# mini-in-a-1.net
KiCad netlist of a schematic drawn in EAGLE
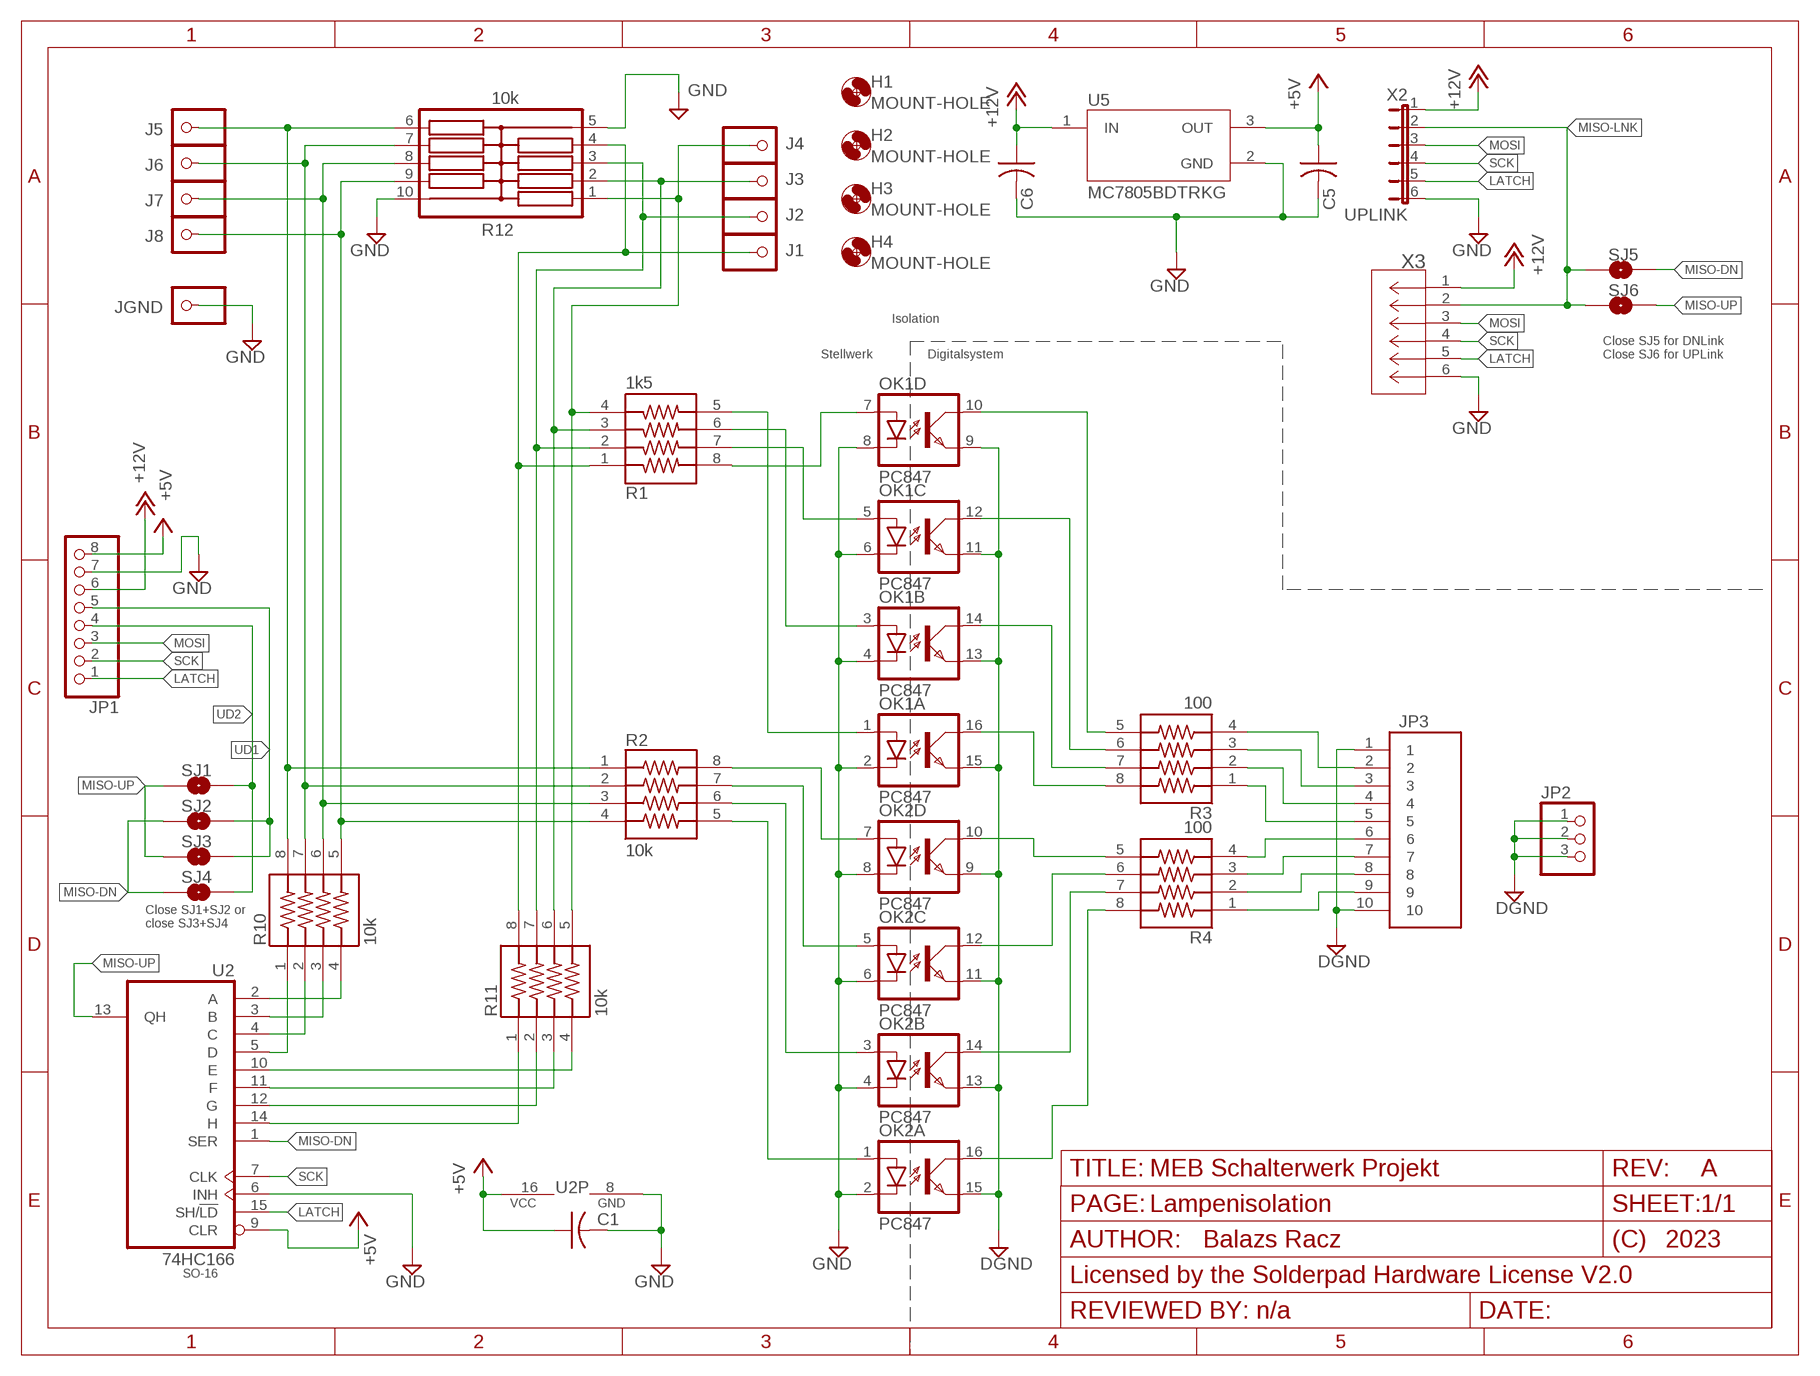
[diagram p0: schematic, sheet 1]

(export (version "E")
  (design (tool "Eeschema 10.0.6"))
  (components
    (comp (ref "C1")
      (value "C-USC0805")
      (footprint "eagle-import:C0805")
      (libsource (lib "eagle-import") (part "C-USC0805"))
    )
    (comp (ref "C5")
      (value "C-USC0805")
      (footprint "eagle-import:C0805")
      (libsource (lib "eagle-import") (part "C-USC0805"))
    )
    (comp (ref "C6")
      (value "C-USC0805")
      (footprint "eagle-import:C0805")
      (libsource (lib "eagle-import") (part "C-USC0805"))
    )
    (comp (ref "H1")
      (value "MOUNT-HOLE")
      (footprint "eagle-import:MOUNT-HOLE-2,8")
      (libsource (lib "eagle-import") (part "MOUNT-HOLE"))
    )
    (comp (ref "H2")
      (value "MOUNT-HOLE")
      (footprint "eagle-import:MOUNT-HOLE-2,8")
      (libsource (lib "eagle-import") (part "MOUNT-HOLE"))
    )
    (comp (ref "H3")
      (value "MOUNT-HOLE")
      (footprint "eagle-import:MOUNT-HOLE-2,8")
      (libsource (lib "eagle-import") (part "MOUNT-HOLE"))
    )
    (comp (ref "H4")
      (value "MOUNT-HOLE")
      (footprint "eagle-import:MOUNT-HOLE-2,8")
      (libsource (lib "eagle-import") (part "MOUNT-HOLE"))
    )
    (comp (ref "J1")
      (value "LARGE-SOLDERPADWITH-HOLE")
      (footprint "eagle-import:LARGE-SOLDERPAD-WITH-HOLES")
      (libsource (lib "eagle-import") (part "LARGE-SOLDERPADWITH-HOLE"))
    )
    (comp (ref "J2")
      (value "LARGE-SOLDERPADWITH-HOLE")
      (footprint "eagle-import:LARGE-SOLDERPAD-WITH-HOLES")
      (libsource (lib "eagle-import") (part "LARGE-SOLDERPADWITH-HOLE"))
    )
    (comp (ref "J3")
      (value "LARGE-SOLDERPADWITH-HOLE")
      (footprint "eagle-import:LARGE-SOLDERPAD-WITH-HOLES")
      (libsource (lib "eagle-import") (part "LARGE-SOLDERPADWITH-HOLE"))
    )
    (comp (ref "J4")
      (value "LARGE-SOLDERPADWITH-HOLE")
      (footprint "eagle-import:LARGE-SOLDERPAD-WITH-HOLES")
      (libsource (lib "eagle-import") (part "LARGE-SOLDERPADWITH-HOLE"))
    )
    (comp (ref "J5")
      (value "LARGE-SOLDERPADWITH-HOLE")
      (footprint "eagle-import:LARGE-SOLDERPAD-WITH-HOLES")
      (libsource (lib "eagle-import") (part "LARGE-SOLDERPADWITH-HOLE"))
    )
    (comp (ref "J6")
      (value "LARGE-SOLDERPADWITH-HOLE")
      (footprint "eagle-import:LARGE-SOLDERPAD-WITH-HOLES")
      (libsource (lib "eagle-import") (part "LARGE-SOLDERPADWITH-HOLE"))
    )
    (comp (ref "J7")
      (value "LARGE-SOLDERPADWITH-HOLE")
      (footprint "eagle-import:LARGE-SOLDERPAD-WITH-HOLES")
      (libsource (lib "eagle-import") (part "LARGE-SOLDERPADWITH-HOLE"))
    )
    (comp (ref "J8")
      (value "LARGE-SOLDERPADWITH-HOLE")
      (footprint "eagle-import:LARGE-SOLDERPAD-WITH-HOLES")
      (libsource (lib "eagle-import") (part "LARGE-SOLDERPADWITH-HOLE"))
    )
    (comp (ref "JGND")
      (value "LARGE-SOLDERPADWITH-HOLE")
      (footprint "eagle-import:LARGE-SOLDERPAD-WITH-HOLES")
      (libsource (lib "eagle-import") (part "LARGE-SOLDERPADWITH-HOLE"))
    )
    (comp (ref "JP1")
      (value "PINHD-1X8")
      (footprint "eagle-import:1X08")
      (libsource (lib "eagle-import") (part "PINHD-1X8"))
    )
    (comp (ref "JP2")
      (value "PINHD-1X3")
      (footprint "eagle-import:1X03")
      (libsource (lib "eagle-import") (part "PINHD-1X3"))
    )
    (comp (ref "JP3")
      (value "TE-CON-MTA150-RA-HEADER-1-640457-0")
      (footprint "eagle-import:TE_1-640457-0")
      (fields (field (name "MANUFACTURER") "TE"))
      (libsource (lib "eagle-import") (part "TE-CON-MTA150-RA-HEADER-1-640457-0"))
    )
    (comp (ref "OK1")
      (value "PC847")
      (footprint "eagle-import:DIL16")
      (libsource (lib "eagle-import") (part "PC847"))
    )
    (comp (ref "OK2")
      (value "PC847")
      (footprint "eagle-import:DIL16")
      (libsource (lib "eagle-import") (part "PC847"))
    )
    (comp (ref "R1")
      (value "1k5")
      (footprint "eagle-import:RESCAXS127P508X320X70-8N")
      (fields (field (name "MANUFACTURER") "Yageo"))
      (libsource (lib "eagle-import") (part "RES-NET-YC324-JK-0710KL"))
    )
    (comp (ref "R2")
      (value "10k")
      (footprint "eagle-import:RESCAXS127P508X320X70-8N")
      (fields (field (name "MANUFACTURER") "Yageo"))
      (libsource (lib "eagle-import") (part "RES-NET-YC324-JK-0710KL"))
    )
    (comp (ref "R3")
      (value "100")
      (footprint "eagle-import:RESCAXS127P508X320X70-8N")
      (fields (field (name "MANUFACTURER") "Yageo"))
      (libsource (lib "eagle-import") (part "RES-NET-YC324-JK-0710KL"))
    )
    (comp (ref "R4")
      (value "100")
      (footprint "eagle-import:RESCAXS127P508X320X70-8N")
      (fields (field (name "MANUFACTURER") "Yageo"))
      (libsource (lib "eagle-import") (part "RES-NET-YC324-JK-0710KL"))
    )
    (comp (ref "R10")
      (value "10k")
      (footprint "eagle-import:RESCAXS127P508X320X70-8N")
      (fields (field (name "MANUFACTURER") "Yageo"))
      (libsource (lib "eagle-import") (part "RES-NET-YC324-JK-0710KL"))
    )
    (comp (ref "R11")
      (value "10k")
      (footprint "eagle-import:RESCAXS127P508X320X70-8N")
      (fields (field (name "MANUFACTURER") "Yageo"))
      (libsource (lib "eagle-import") (part "RES-NET-YC324-JK-0710KL"))
    )
    (comp (ref "R12")
      (value "10k")
      (footprint "eagle-import:RESCAV127P640X310X70-10N")
      (fields (field (name "MANUFACTURER") "CTS"))
      (libsource (lib "eagle-import") (part "RES-NET-745C101103JP"))
    )
    (comp (ref "SJ1")
      (value "SJRND2")
      (footprint "eagle-import:SJ_RND2")
      (libsource (lib "eagle-import") (part "SJRND2"))
    )
    (comp (ref "SJ2")
      (value "SJRND2")
      (footprint "eagle-import:SJ_RND2")
      (libsource (lib "eagle-import") (part "SJRND2"))
    )
    (comp (ref "SJ3")
      (value "SJRND2")
      (footprint "eagle-import:SJ_RND2")
      (libsource (lib "eagle-import") (part "SJRND2"))
    )
    (comp (ref "SJ4")
      (value "SJRND2")
      (footprint "eagle-import:SJ_RND2")
      (libsource (lib "eagle-import") (part "SJRND2"))
    )
    (comp (ref "SJ5")
      (value "SJRND2")
      (footprint "eagle-import:SJ_RND2")
      (libsource (lib "eagle-import") (part "SJRND2"))
    )
    (comp (ref "SJ6")
      (value "SJRND2")
      (footprint "eagle-import:SJ_RND2")
      (libsource (lib "eagle-import") (part "SJRND2"))
    )
    (comp (ref "U2")
      (value "74HC166")
      (footprint "eagle-import:SO16")
      (libsource (lib "eagle-import") (part "74166D"))
    )
    (comp (ref "U5")
      (value "MC7805BDTRKG")
      (footprint "eagle-import:DPAK229P990X238-4N")
      (fields (field (name "MANUFACTURER") "ON Semiconductor"))
      (libsource (lib "eagle-import") (part "MC7805BDTRKG"))
    )
    (comp (ref "X2")
      (value "UPLINK")
      (footprint "eagle-import:JP6F-FEM")
      (libsource (lib "eagle-import") (part "JP6-FLATFEMALE"))
    )
    (comp (ref "X3")
      (value "MOLEX_530480610CON_530480610_MOL")
      (footprint "eagle-import:CON_530480610_MOL")
      (fields
        (field (name "MANUFACTURER_PART_NUMBER") "530480610")
        (field (name "COPYRIGHT") "Copyright (C) 2023 Ultra Librarian. All rights reserved.")
      )
      (libsource (lib "eagle-import") (part "MOLEX_530480610CON_530480610_MOL"))
    )
  )
  (nets
    (net (code "1") (name "+5V") (class "Default")
      (node (ref "C1") (pin "1") (pinfunction "1_1") (pintype "passive"))
      (node (ref "C5") (pin "1") (pinfunction "1_1") (pintype "passive"))
      (node (ref "JP1") (pin "8") (pinfunction "8_8") (pintype "passive"))
      (node (ref "U2") (pin "16") (pinfunction "VCC_16") (pintype "power_in"))
      (node (ref "U2") (pin "9") (pinfunction "CLR_9") (pintype "input"))
      (node (ref "U5") (pin "3") (pinfunction "OUT_3") (pintype "output"))
    )
    (net (code "2") (name "+12V") (class "Default")
      (node (ref "C6") (pin "1") (pinfunction "1_1") (pintype "passive"))
      (node (ref "JP1") (pin "6") (pinfunction "6_6") (pintype "passive"))
      (node (ref "U5") (pin "1") (pinfunction "IN_1") (pintype "input"))
      (node (ref "X2") (pin "1") (pinfunction "1_1") (pintype "passive"))
      (node (ref "X3") (pin "1") (pinfunction "1_1") (pintype "passive"))
    )
    (net (code "3") (name "DGND") (class "Default")
      (node (ref "JP2") (pin "1") (pinfunction "1_1") (pintype "passive"))
      (node (ref "JP2") (pin "2") (pinfunction "2_2") (pintype "passive"))
      (node (ref "JP2") (pin "3") (pinfunction "3_3") (pintype "passive"))
      (node (ref "JP3") (pin "1") (pinfunction "1_1") (pintype "passive"))
      (node (ref "JP3") (pin "10") (pinfunction "10_10") (pintype "passive"))
      (node (ref "OK1") (pin "11") (pinfunction "EMIT_11") (pintype "passive"))
      (node (ref "OK1") (pin "13") (pinfunction "EMIT_13") (pintype "passive"))
      (node (ref "OK1") (pin "15") (pinfunction "EMIT_15") (pintype "passive"))
      (node (ref "OK1") (pin "9") (pinfunction "EMIT_9") (pintype "passive"))
      (node (ref "OK2") (pin "11") (pinfunction "EMIT_11") (pintype "passive"))
      (node (ref "OK2") (pin "13") (pinfunction "EMIT_13") (pintype "passive"))
      (node (ref "OK2") (pin "15") (pinfunction "EMIT_15") (pintype "passive"))
      (node (ref "OK2") (pin "9") (pinfunction "EMIT_9") (pintype "passive"))
    )
    (net (code "4") (name "GND") (class "Default")
      (node (ref "C1") (pin "2") (pinfunction "2_2") (pintype "passive"))
      (node (ref "C5") (pin "2") (pinfunction "2_2") (pintype "passive"))
      (node (ref "C6") (pin "2") (pinfunction "2_2") (pintype "passive"))
      (node (ref "JGND") (pin "P$1") (pinfunction "1_P$1") (pintype "passive"))
      (node (ref "JP1") (pin "7") (pinfunction "7_7") (pintype "passive"))
      (node (ref "OK1") (pin "2") (pinfunction "C_2") (pintype "passive"))
      (node (ref "OK1") (pin "4") (pinfunction "C_4") (pintype "passive"))
      (node (ref "OK1") (pin "6") (pinfunction "C_6") (pintype "passive"))
      (node (ref "OK1") (pin "8") (pinfunction "C_8") (pintype "passive"))
      (node (ref "OK2") (pin "2") (pinfunction "C_2") (pintype "passive"))
      (node (ref "OK2") (pin "4") (pinfunction "C_4") (pintype "passive"))
      (node (ref "OK2") (pin "6") (pinfunction "C_6") (pintype "passive"))
      (node (ref "OK2") (pin "8") (pinfunction "C_8") (pintype "passive"))
      (node (ref "R12") (pin "10") (pinfunction "10_10") (pintype "passive"))
      (node (ref "R12") (pin "5") (pinfunction "5_5") (pintype "passive"))
      (node (ref "U2") (pin "6") (pinfunction "INH_6") (pintype "input"))
      (node (ref "U2") (pin "8") (pinfunction "GND_8") (pintype "power_in"))
      (node (ref "U5") (pin "2") (pinfunction "GND_2") (pintype "power_in"))
      (node (ref "X2") (pin "6") (pinfunction "6_6") (pintype "passive"))
      (node (ref "X3") (pin "6") (pinfunction "6_6") (pintype "passive"))
    )
    (net (code "5") (name "LATCH") (class "Default")
      (node (ref "JP1") (pin "1") (pinfunction "1_1") (pintype "passive"))
      (node (ref "U2") (pin "15") (pinfunction "SH/~{LD}_15") (pintype "input"))
      (node (ref "X2") (pin "5") (pinfunction "5_5") (pintype "passive"))
      (node (ref "X3") (pin "5") (pinfunction "5_5") (pintype "passive"))
    )
    (net (code "6") (name "MISO-DN") (class "Default")
      (node (ref "SJ2") (pin "P$1") (pinfunction "1_P$1") (pintype "passive"))
      (node (ref "SJ4") (pin "P$1") (pinfunction "1_P$1") (pintype "passive"))
      (node (ref "SJ5") (pin "P$1") (pinfunction "1_P$1") (pintype "passive"))
      (node (ref "U2") (pin "1") (pinfunction "SER_1") (pintype "input"))
    )
    (net (code "7") (name "MISO-LNK") (class "Default")
      (node (ref "SJ5") (pin "P$2") (pinfunction "2_P$2") (pintype "passive"))
      (node (ref "SJ6") (pin "P$2") (pinfunction "2_P$2") (pintype "passive"))
      (node (ref "X2") (pin "2") (pinfunction "2_2") (pintype "passive"))
      (node (ref "X3") (pin "2") (pinfunction "2_2") (pintype "passive"))
    )
    (net (code "8") (name "MISO-UP") (class "Default")
      (node (ref "SJ1") (pin "P$1") (pinfunction "1_P$1") (pintype "passive"))
      (node (ref "SJ3") (pin "P$1") (pinfunction "1_P$1") (pintype "passive"))
      (node (ref "SJ6") (pin "P$1") (pinfunction "1_P$1") (pintype "passive"))
      (node (ref "U2") (pin "13") (pinfunction "QH_13") (pintype "output"))
    )
    (net (code "9") (name "MOSI") (class "Default")
      (node (ref "JP1") (pin "3") (pinfunction "3_3") (pintype "passive"))
      (node (ref "X2") (pin "3") (pinfunction "3_3") (pintype "passive"))
      (node (ref "X3") (pin "3") (pinfunction "3_3") (pintype "passive"))
    )
    (net (code "10") (name "Net-(J1-1)") (class "Default")
      (node (ref "J1") (pin "P$1") (pinfunction "1_P$1") (pintype "passive"))
      (node (ref "R1") (pin "1") (pinfunction "1_1") (pintype "passive"))
      (node (ref "R11") (pin "8") (pinfunction "8_8") (pintype "passive"))
      (node (ref "R12") (pin "4") (pinfunction "4_4") (pintype "passive"))
    )
    (net (code "11") (name "Net-(J2-1)") (class "Default")
      (node (ref "J2") (pin "P$1") (pinfunction "1_P$1") (pintype "passive"))
      (node (ref "R1") (pin "2") (pinfunction "2_2") (pintype "passive"))
      (node (ref "R11") (pin "7") (pinfunction "7_7") (pintype "passive"))
      (node (ref "R12") (pin "3") (pinfunction "3_3") (pintype "passive"))
    )
    (net (code "12") (name "Net-(J3-1)") (class "Default")
      (node (ref "J3") (pin "P$1") (pinfunction "1_P$1") (pintype "passive"))
      (node (ref "R1") (pin "3") (pinfunction "3_3") (pintype "passive"))
      (node (ref "R11") (pin "6") (pinfunction "6_6") (pintype "passive"))
      (node (ref "R12") (pin "2") (pinfunction "2_2") (pintype "passive"))
    )
    (net (code "13") (name "Net-(J4-1)") (class "Default")
      (node (ref "J4") (pin "P$1") (pinfunction "1_P$1") (pintype "passive"))
      (node (ref "R1") (pin "4") (pinfunction "4_4") (pintype "passive"))
      (node (ref "R11") (pin "5") (pinfunction "5_5") (pintype "passive"))
      (node (ref "R12") (pin "1") (pinfunction "1_1") (pintype "passive"))
    )
    (net (code "14") (name "Net-(J5-1)") (class "Default")
      (node (ref "J5") (pin "P$1") (pinfunction "1_P$1") (pintype "passive"))
      (node (ref "R10") (pin "8") (pinfunction "8_8") (pintype "passive"))
      (node (ref "R12") (pin "6") (pinfunction "6_6") (pintype "passive"))
      (node (ref "R2") (pin "1") (pinfunction "1_1") (pintype "passive"))
    )
    (net (code "15") (name "Net-(J6-1)") (class "Default")
      (node (ref "J6") (pin "P$1") (pinfunction "1_P$1") (pintype "passive"))
      (node (ref "R10") (pin "7") (pinfunction "7_7") (pintype "passive"))
      (node (ref "R12") (pin "7") (pinfunction "7_7") (pintype "passive"))
      (node (ref "R2") (pin "2") (pinfunction "2_2") (pintype "passive"))
    )
    (net (code "16") (name "Net-(J7-1)") (class "Default")
      (node (ref "J7") (pin "P$1") (pinfunction "1_P$1") (pintype "passive"))
      (node (ref "R10") (pin "6") (pinfunction "6_6") (pintype "passive"))
      (node (ref "R12") (pin "8") (pinfunction "8_8") (pintype "passive"))
      (node (ref "R2") (pin "3") (pinfunction "3_3") (pintype "passive"))
    )
    (net (code "17") (name "Net-(J8-1)") (class "Default")
      (node (ref "J8") (pin "P$1") (pinfunction "1_P$1") (pintype "passive"))
      (node (ref "R10") (pin "5") (pinfunction "5_5") (pintype "passive"))
      (node (ref "R12") (pin "9") (pinfunction "9_9") (pintype "passive"))
      (node (ref "R2") (pin "4") (pinfunction "4_4") (pintype "passive"))
    )
    (net (code "18") (name "Net-(JP3-Pad2)") (class "Default")
      (node (ref "JP3") (pin "2") (pinfunction "2_2") (pintype "passive"))
      (node (ref "R3") (pin "4") (pinfunction "4_4") (pintype "passive"))
    )
    (net (code "19") (name "Net-(JP3-Pad3)") (class "Default")
      (node (ref "JP3") (pin "3") (pinfunction "3_3") (pintype "passive"))
      (node (ref "R3") (pin "3") (pinfunction "3_3") (pintype "passive"))
    )
    (net (code "20") (name "Net-(JP3-Pad4)") (class "Default")
      (node (ref "JP3") (pin "4") (pinfunction "4_4") (pintype "passive"))
      (node (ref "R3") (pin "2") (pinfunction "2_2") (pintype "passive"))
    )
    (net (code "21") (name "Net-(JP3-Pad5)") (class "Default")
      (node (ref "JP3") (pin "5") (pinfunction "5_5") (pintype "passive"))
      (node (ref "R3") (pin "1") (pinfunction "1_1") (pintype "passive"))
    )
    (net (code "22") (name "Net-(JP3-Pad6)") (class "Default")
      (node (ref "JP3") (pin "6") (pinfunction "6_6") (pintype "passive"))
      (node (ref "R4") (pin "4") (pinfunction "4_4") (pintype "passive"))
    )
    (net (code "23") (name "Net-(JP3-Pad7)") (class "Default")
      (node (ref "JP3") (pin "7") (pinfunction "7_7") (pintype "passive"))
      (node (ref "R4") (pin "3") (pinfunction "3_3") (pintype "passive"))
    )
    (net (code "24") (name "Net-(JP3-Pad8)") (class "Default")
      (node (ref "JP3") (pin "8") (pinfunction "8_8") (pintype "passive"))
      (node (ref "R4") (pin "2") (pinfunction "2_2") (pintype "passive"))
    )
    (net (code "25") (name "Net-(JP3-Pad9)") (class "Default")
      (node (ref "JP3") (pin "9") (pinfunction "9_9") (pintype "passive"))
      (node (ref "R4") (pin "1") (pinfunction "1_1") (pintype "passive"))
    )
    (net (code "26") (name "Net-(OK1A-A)") (class "Default")
      (node (ref "OK1") (pin "1") (pinfunction "A_1") (pintype "passive"))
      (node (ref "R1") (pin "5") (pinfunction "5_5") (pintype "passive"))
    )
    (net (code "27") (name "Net-(OK1A-COL)") (class "Default")
      (node (ref "OK1") (pin "16") (pinfunction "COL_16") (pintype "passive"))
      (node (ref "R3") (pin "8") (pinfunction "8_8") (pintype "passive"))
    )
    (net (code "28") (name "Net-(OK1B-A)") (class "Default")
      (node (ref "OK1") (pin "3") (pinfunction "A_3") (pintype "passive"))
      (node (ref "R1") (pin "6") (pinfunction "6_6") (pintype "passive"))
    )
    (net (code "29") (name "Net-(OK1B-COL)") (class "Default")
      (node (ref "OK1") (pin "14") (pinfunction "COL_14") (pintype "passive"))
      (node (ref "R3") (pin "7") (pinfunction "7_7") (pintype "passive"))
    )
    (net (code "30") (name "Net-(OK1C-A)") (class "Default")
      (node (ref "OK1") (pin "5") (pinfunction "A_5") (pintype "passive"))
      (node (ref "R1") (pin "7") (pinfunction "7_7") (pintype "passive"))
    )
    (net (code "31") (name "Net-(OK1C-COL)") (class "Default")
      (node (ref "OK1") (pin "12") (pinfunction "COL_12") (pintype "passive"))
      (node (ref "R3") (pin "6") (pinfunction "6_6") (pintype "passive"))
    )
    (net (code "32") (name "Net-(OK1D-A)") (class "Default")
      (node (ref "OK1") (pin "7") (pinfunction "A_7") (pintype "passive"))
      (node (ref "R1") (pin "8") (pinfunction "8_8") (pintype "passive"))
    )
    (net (code "33") (name "Net-(OK1D-COL)") (class "Default")
      (node (ref "OK1") (pin "10") (pinfunction "COL_10") (pintype "passive"))
      (node (ref "R3") (pin "5") (pinfunction "5_5") (pintype "passive"))
    )
    (net (code "34") (name "Net-(OK2A-A)") (class "Default")
      (node (ref "OK2") (pin "1") (pinfunction "A_1") (pintype "passive"))
      (node (ref "R2") (pin "5") (pinfunction "5_5") (pintype "passive"))
    )
    (net (code "35") (name "Net-(OK2A-COL)") (class "Default")
      (node (ref "OK2") (pin "16") (pinfunction "COL_16") (pintype "passive"))
      (node (ref "R4") (pin "8") (pinfunction "8_8") (pintype "passive"))
    )
    (net (code "36") (name "Net-(OK2B-A)") (class "Default")
      (node (ref "OK2") (pin "3") (pinfunction "A_3") (pintype "passive"))
      (node (ref "R2") (pin "6") (pinfunction "6_6") (pintype "passive"))
    )
    (net (code "37") (name "Net-(OK2B-COL)") (class "Default")
      (node (ref "OK2") (pin "14") (pinfunction "COL_14") (pintype "passive"))
      (node (ref "R4") (pin "7") (pinfunction "7_7") (pintype "passive"))
    )
    (net (code "38") (name "Net-(OK2C-A)") (class "Default")
      (node (ref "OK2") (pin "5") (pinfunction "A_5") (pintype "passive"))
      (node (ref "R2") (pin "7") (pinfunction "7_7") (pintype "passive"))
    )
    (net (code "39") (name "Net-(OK2C-COL)") (class "Default")
      (node (ref "OK2") (pin "12") (pinfunction "COL_12") (pintype "passive"))
      (node (ref "R4") (pin "6") (pinfunction "6_6") (pintype "passive"))
    )
    (net (code "40") (name "Net-(OK2D-A)") (class "Default")
      (node (ref "OK2") (pin "7") (pinfunction "A_7") (pintype "passive"))
      (node (ref "R2") (pin "8") (pinfunction "8_8") (pintype "passive"))
    )
    (net (code "41") (name "Net-(OK2D-COL)") (class "Default")
      (node (ref "OK2") (pin "10") (pinfunction "COL_10") (pintype "passive"))
      (node (ref "R4") (pin "5") (pinfunction "5_5") (pintype "passive"))
    )
    (net (code "42") (name "Net-(U2A-A)") (class "Default")
      (node (ref "R10") (pin "4") (pinfunction "4_4") (pintype "passive"))
      (node (ref "U2") (pin "2") (pinfunction "A_2") (pintype "input"))
    )
    (net (code "43") (name "Net-(U2A-B)") (class "Default")
      (node (ref "R10") (pin "3") (pinfunction "3_3") (pintype "passive"))
      (node (ref "U2") (pin "3") (pinfunction "B_3") (pintype "input"))
    )
    (net (code "44") (name "Net-(U2A-C)") (class "Default")
      (node (ref "R10") (pin "2") (pinfunction "2_2") (pintype "passive"))
      (node (ref "U2") (pin "4") (pinfunction "C_4") (pintype "input"))
    )
    (net (code "45") (name "Net-(U2A-D)") (class "Default")
      (node (ref "R10") (pin "1") (pinfunction "1_1") (pintype "passive"))
      (node (ref "U2") (pin "5") (pinfunction "D_5") (pintype "input"))
    )
    (net (code "46") (name "Net-(U2A-E)") (class "Default")
      (node (ref "R11") (pin "4") (pinfunction "4_4") (pintype "passive"))
      (node (ref "U2") (pin "10") (pinfunction "E_10") (pintype "input"))
    )
    (net (code "47") (name "Net-(U2A-F)") (class "Default")
      (node (ref "R11") (pin "3") (pinfunction "3_3") (pintype "passive"))
      (node (ref "U2") (pin "11") (pinfunction "F_11") (pintype "input"))
    )
    (net (code "48") (name "Net-(U2A-G)") (class "Default")
      (node (ref "R11") (pin "2") (pinfunction "2_2") (pintype "passive"))
      (node (ref "U2") (pin "12") (pinfunction "G_12") (pintype "input"))
    )
    (net (code "49") (name "Net-(U2A-H)") (class "Default")
      (node (ref "R11") (pin "1") (pinfunction "1_1") (pintype "passive"))
      (node (ref "U2") (pin "14") (pinfunction "H_14") (pintype "input"))
    )
    (net (code "50") (name "SCK") (class "Default")
      (node (ref "JP1") (pin "2") (pinfunction "2_2") (pintype "passive"))
      (node (ref "U2") (pin "7") (pinfunction "CLK_7") (pintype "input"))
      (node (ref "X2") (pin "4") (pinfunction "4_4") (pintype "passive"))
      (node (ref "X3") (pin "4") (pinfunction "4_4") (pintype "passive"))
    )
    (net (code "51") (name "UD1") (class "Default")
      (node (ref "JP1") (pin "5") (pinfunction "5_5") (pintype "passive"))
      (node (ref "SJ2") (pin "P$2") (pinfunction "2_P$2") (pintype "passive"))
      (node (ref "SJ3") (pin "P$2") (pinfunction "2_P$2") (pintype "passive"))
    )
    (net (code "52") (name "UD2") (class "Default")
      (node (ref "JP1") (pin "4") (pinfunction "4_4") (pintype "passive"))
      (node (ref "SJ1") (pin "P$2") (pinfunction "2_P$2") (pintype "passive"))
      (node (ref "SJ4") (pin "P$2") (pinfunction "2_P$2") (pintype "passive"))
    )
  )
)
